# MQ9_pcb.net
KiCad netlist of a schematic drawn in EAGLE
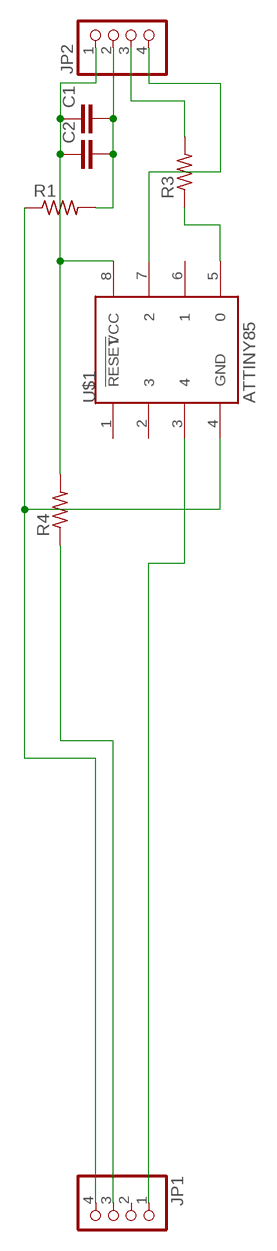
[diagram p0: schematic, sheet 1]

(export (version "E")
  (design (tool "Eeschema 10.0.6"))
  (components
    (comp (ref "C1")
      (value "C2,5-3")
      (footprint "eagle-import:C2.5-3")
      (libsource (lib "eagle-import") (part "C2,5-3"))
    )
    (comp (ref "C2")
      (value "C5/2.5")
      (footprint "eagle-import:C5B2.5")
      (libsource (lib "eagle-import") (part "C5/2.5"))
    )
    (comp (ref "JP1")
      (value "PINHD-1X4")
      (footprint "eagle-import:1X04")
      (libsource (lib "eagle-import") (part "PINHD-1X4"))
    )
    (comp (ref "JP2")
      (value "PINHD-1X4/90")
      (footprint "eagle-import:1X04_90")
      (libsource (lib "eagle-import") (part "PINHD-1X4/90"))
    )
    (comp (ref "R1")
      (value "R-US_0204/5")
      (footprint "eagle-import:0204_5")
      (libsource (lib "eagle-import") (part "R-US_0204/5"))
    )
    (comp (ref "R3")
      (value "R-US_0204/5")
      (footprint "eagle-import:0204_5")
      (libsource (lib "eagle-import") (part "R-US_0204/5"))
    )
    (comp (ref "R4")
      (value "R-US_0204/5")
      (footprint "eagle-import:0204_5")
      (libsource (lib "eagle-import") (part "R-US_0204/5"))
    )
    (comp (ref "U$1")
      (value "ATTINY85")
      (footprint "eagle-import:8P3")
      (libsource (lib "eagle-import") (part "ATTINY85"))
    )
  )
  (nets
    (net (code "1") (name "Net-(C1-Pad2)") (class "Default")
      (node (ref "C1") (pin "2") (pinfunction "2_2") (pintype "passive"))
      (node (ref "C2") (pin "2") (pinfunction "2_2") (pintype "passive"))
      (node (ref "JP2") (pin "2") (pinfunction "2_2") (pintype "passive"))
      (node (ref "R1") (pin "2") (pinfunction "2_2") (pintype "passive"))
    )
    (net (code "2") (name "Net-(JP1-Pad3)") (class "Default")
      (node (ref "JP1") (pin "3") (pinfunction "3_3") (pintype "passive"))
      (node (ref "R4") (pin "1") (pinfunction "1_1") (pintype "passive"))
    )
    (net (code "3") (name "Net-(JP2-Pad3)") (class "Default")
      (node (ref "JP2") (pin "3") (pinfunction "3_3") (pintype "passive"))
      (node (ref "R3") (pin "2") (pinfunction "2_2") (pintype "passive"))
    )
    (net (code "4") (name "Net-(U$1-0)") (class "Default")
      (node (ref "R3") (pin "1") (pinfunction "1_1") (pintype "passive"))
      (node (ref "U$1") (pin "5") (pinfunction "0_5") (pintype "bidirectional"))
    )
    (net (code "5") (name "Net-(U$1-2)") (class "Default")
      (node (ref "JP2") (pin "4") (pinfunction "4_4") (pintype "passive"))
      (node (ref "U$1") (pin "7") (pinfunction "2_7") (pintype "bidirectional"))
    )
    (net (code "6") (name "Net-(U$1-4)") (class "Default")
      (node (ref "JP1") (pin "1") (pinfunction "1_1") (pintype "passive"))
      (node (ref "U$1") (pin "3") (pinfunction "4_3") (pintype "bidirectional"))
    )
    (net (code "7") (name "Net-(U$1-GND)") (class "Default")
      (node (ref "JP1") (pin "4") (pinfunction "4_4") (pintype "passive"))
      (node (ref "R1") (pin "1") (pinfunction "1_1") (pintype "passive"))
      (node (ref "U$1") (pin "4") (pinfunction "GND_4") (pintype "power_in"))
    )
    (net (code "8") (name "Net-(U$1-VCC)") (class "Default")
      (node (ref "C1") (pin "1") (pinfunction "1_1") (pintype "passive"))
      (node (ref "C2") (pin "1") (pinfunction "1_1") (pintype "passive"))
      (node (ref "JP2") (pin "1") (pinfunction "1_1") (pintype "passive"))
      (node (ref "R4") (pin "2") (pinfunction "2_2") (pintype "passive"))
      (node (ref "U$1") (pin "8") (pinfunction "VCC_8") (pintype "power_in"))
    )
    (net (code "9") (name "unconnected-(JP1-Pad2)") (class "Default")
      (node (ref "JP1") (pin "2") (pinfunction "2_2") (pintype "passive"))
    )
    (net (code "10") (name "unconnected-(U$1-1-Pad6)") (class "Default")
      (node (ref "U$1") (pin "6") (pinfunction "1_6") (pintype "bidirectional"))
    )
    (net (code "11") (name "unconnected-(U$1-3-Pad2)") (class "Default")
      (node (ref "U$1") (pin "2") (pinfunction "3_2") (pintype "bidirectional"))
    )
    (net (code "12") (name "unconnected-(U$1-~{RESET}-Pad1)") (class "Default")
      (node (ref "U$1") (pin "1") (pinfunction "~{RESET}_1") (pintype "bidirectional"))
    )
  )
)
